# ORD_POT.net
KiCad netlist of a schematic drawn in Altium Designer
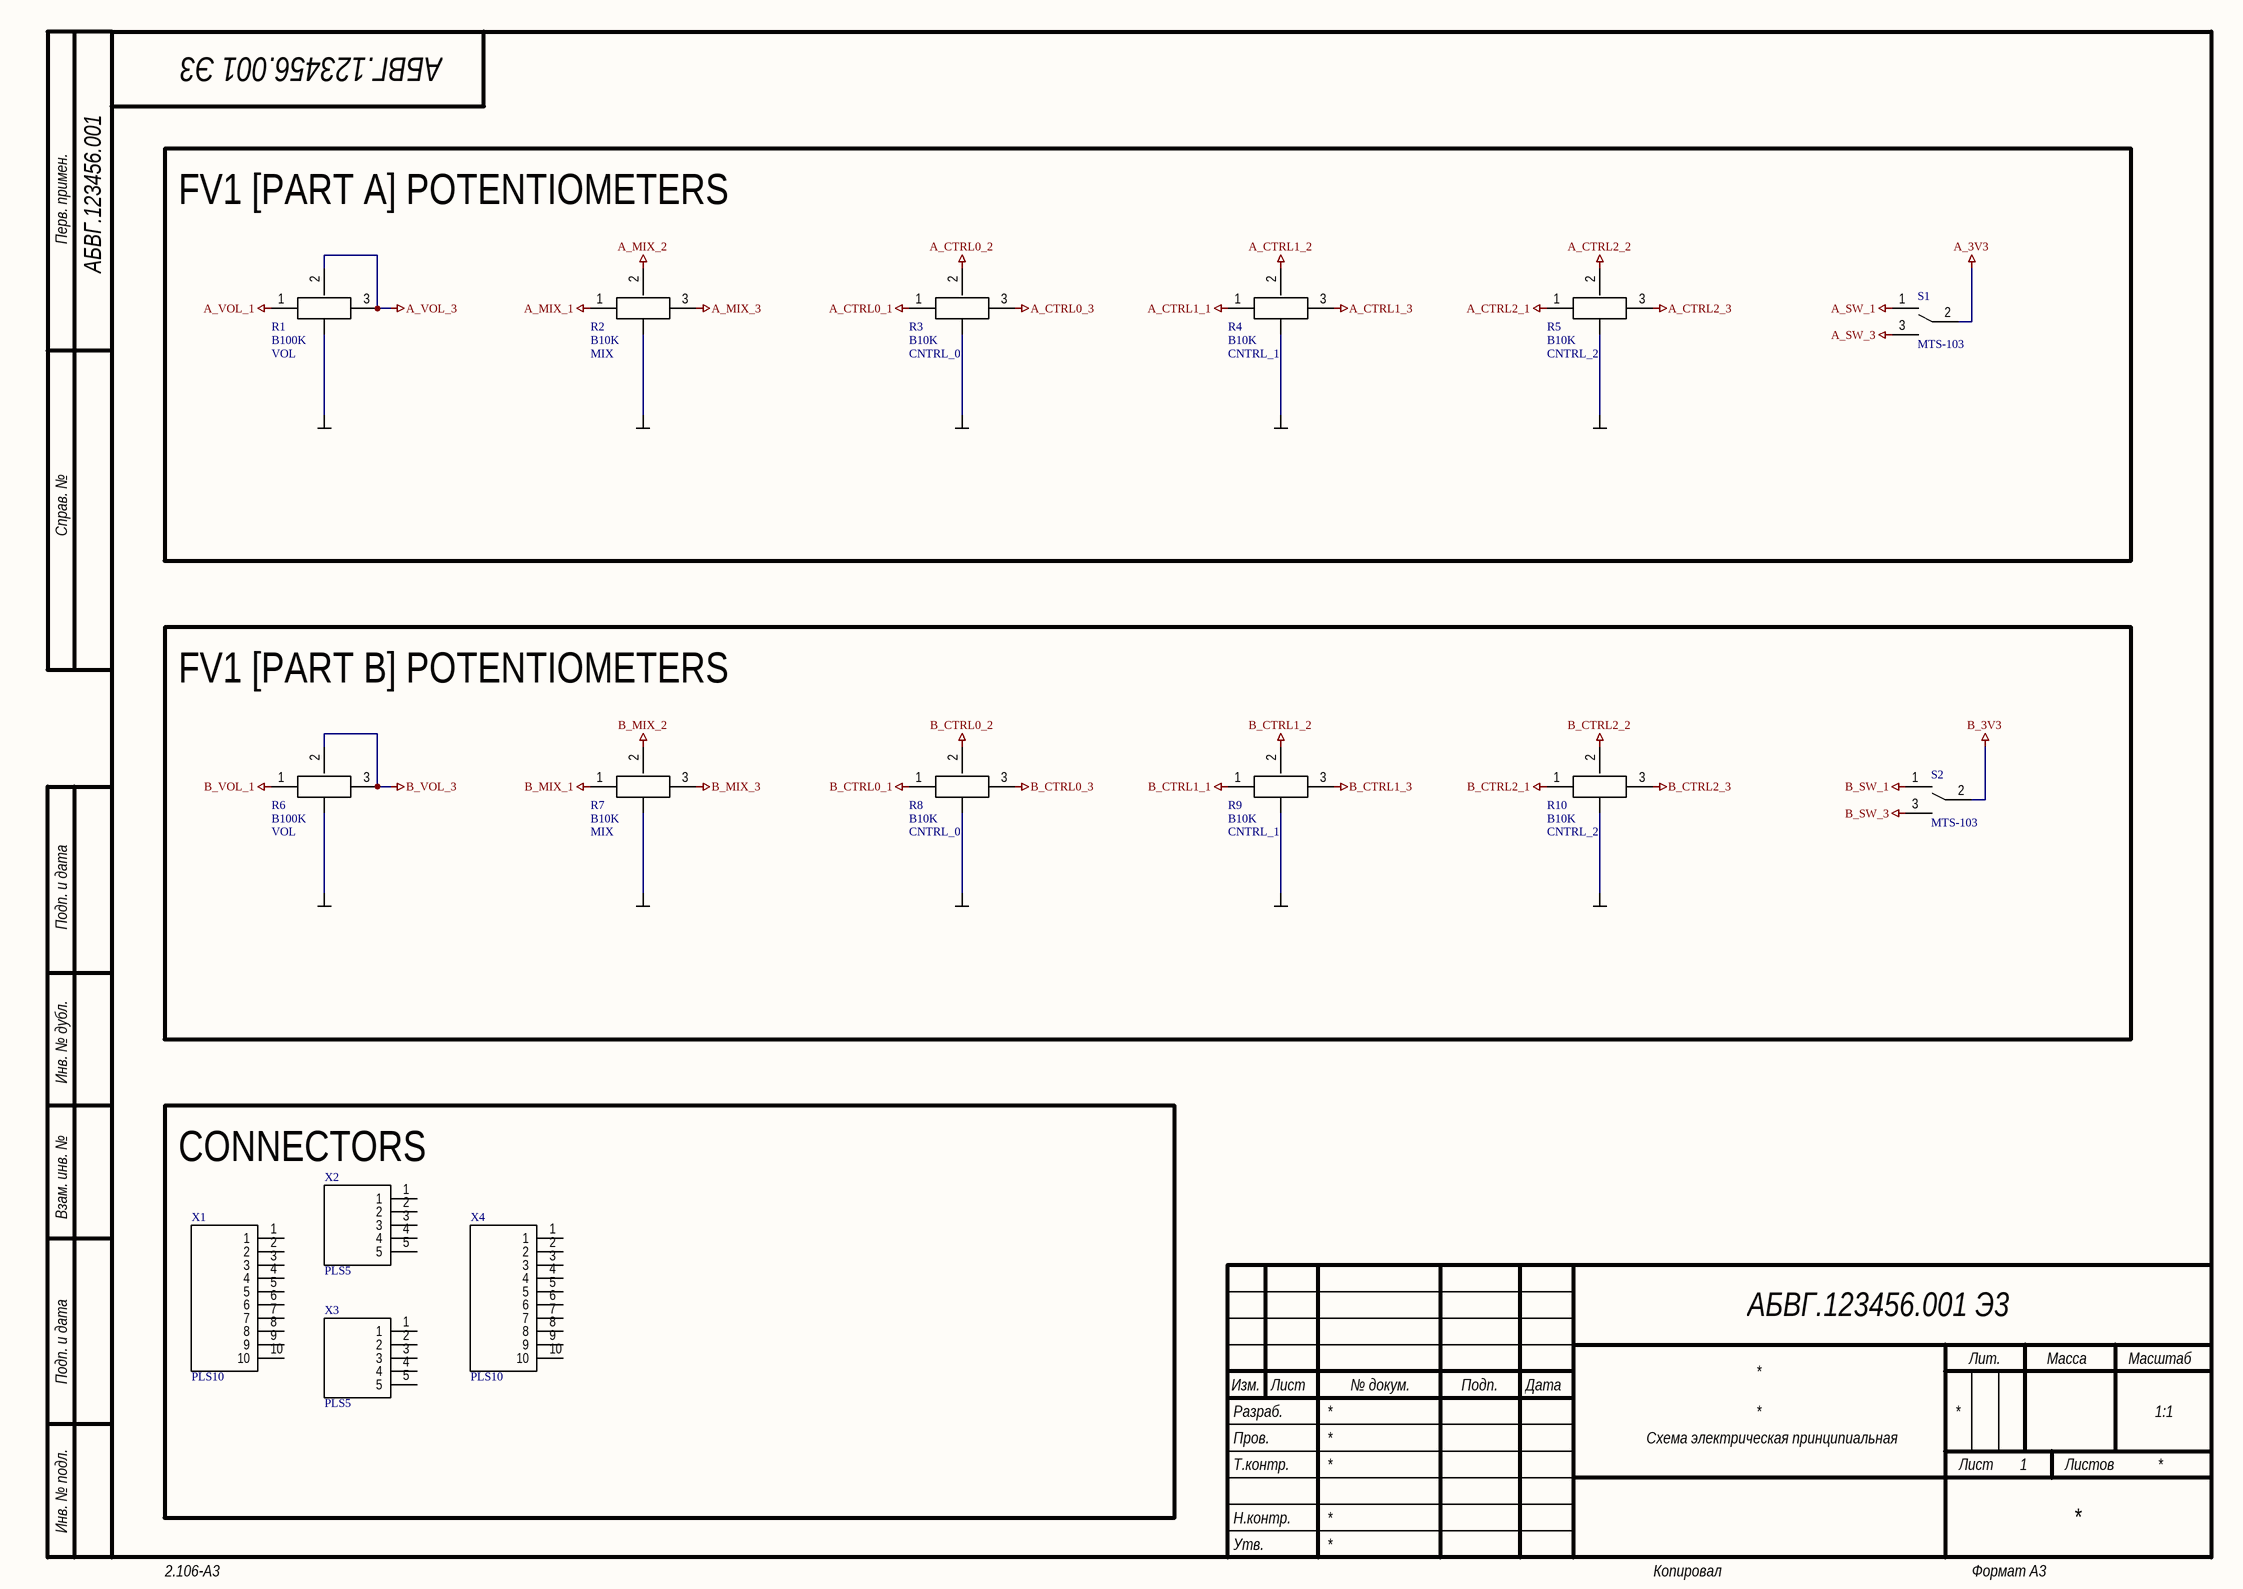
[diagram p0: ORD_POT.SchDoc]

(export (version "E")
  (design (tool "Eeschema 10.0.6"))
  (components
    (comp (ref "R1") (value "B100K") (footprint "RK097") (libsource (lib "Gost_passive_lib") (part "RK097")))
    (comp (ref "R2") (value "B10K") (footprint "RK097") (libsource (lib "Gost_passive_lib") (part "RK097")))
    (comp (ref "R3") (value "B10K") (footprint "RK097") (libsource (lib "Gost_passive_lib") (part "RK097")))
    (comp (ref "R4") (value "B10K") (footprint "RK097") (libsource (lib "Gost_passive_lib") (part "RK097")))
    (comp (ref "R5") (value "B10K") (footprint "RK097") (libsource (lib "Gost_passive_lib") (part "RK097")))
    (comp (ref "R6") (value "B100K") (footprint "RK097") (libsource (lib "Gost_passive_lib") (part "RK097")))
    (comp (ref "R7") (value "B10K") (footprint "RK097") (libsource (lib "Gost_passive_lib") (part "RK097")))
    (comp (ref "R8") (value "B10K") (footprint "RK097") (libsource (lib "Gost_passive_lib") (part "RK097")))
    (comp (ref "R9") (value "B10K") (footprint "RK097") (libsource (lib "Gost_passive_lib") (part "RK097")))
    (comp (ref "R10") (value "B10K") (footprint "RK097") (libsource (lib "Gost_passive_lib") (part "RK097")))
    (comp (ref "S1")
      (value "MTS-103")
      (footprint "MTS-103")
      (description "Switch, ON-OFF-ON")
      (libsource (lib "Gost_connectors_lib") (part "MTS-103"))
    )
    (comp (ref "S2")
      (value "MTS-103")
      (footprint "MTS-103")
      (description "Switch, ON-OFF-ON")
      (libsource (lib "Gost_connectors_lib") (part "MTS-103"))
    )
    (comp (ref "X1")
      (value "PLS10")
      (footprint "PLS-10")
      (description "2.54 mm")
      (libsource (lib "Gost_connectors_lib") (part "PLS10"))
    )
    (comp (ref "X2")
      (value "PLS5")
      (footprint "pls-5")
      (description "2.54 mm")
      (libsource (lib "Gost_connectors_lib") (part "PLS5"))
    )
    (comp (ref "X3")
      (value "PLS5")
      (footprint "pls-5")
      (description "2.54 mm")
      (libsource (lib "Gost_connectors_lib") (part "PLS5"))
    )
    (comp (ref "X4")
      (value "PLS10")
      (footprint "PLS-10")
      (description "2.54 mm")
      (libsource (lib "Gost_connectors_lib") (part "PLS10"))
    )
  )
  (nets
    (net (code "1") (name "A_3V3") (class "Default")
      (node (ref "S1") (pin "2") (pinfunction "2_2") (pintype "passive"))
    )
    (net (code "2") (name "A_CTRL0_1") (class "Default")
      (node (ref "R3") (pin "1") (pinfunction "1_1") (pintype "passive"))
    )
    (net (code "3") (name "A_CTRL0_2") (class "Default")
      (node (ref "R3") (pin "2") (pinfunction "2_2") (pintype "passive"))
    )
    (net (code "4") (name "A_CTRL0_3") (class "Default")
      (node (ref "R3") (pin "3") (pinfunction "3_3") (pintype "passive"))
    )
    (net (code "5") (name "A_CTRL1_1") (class "Default")
      (node (ref "R4") (pin "1") (pinfunction "1_1") (pintype "passive"))
    )
    (net (code "6") (name "A_CTRL1_2") (class "Default")
      (node (ref "R4") (pin "2") (pinfunction "2_2") (pintype "passive"))
    )
    (net (code "7") (name "A_CTRL1_3") (class "Default")
      (node (ref "R4") (pin "3") (pinfunction "3_3") (pintype "passive"))
    )
    (net (code "8") (name "A_CTRL2_1") (class "Default")
      (node (ref "R5") (pin "1") (pinfunction "1_1") (pintype "passive"))
    )
    (net (code "9") (name "A_CTRL2_2") (class "Default")
      (node (ref "R5") (pin "2") (pinfunction "2_2") (pintype "passive"))
    )
    (net (code "10") (name "A_CTRL2_3") (class "Default")
      (node (ref "R5") (pin "3") (pinfunction "3_3") (pintype "passive"))
    )
    (net (code "11") (name "A_MIX_1") (class "Default")
      (node (ref "R2") (pin "1") (pinfunction "1_1") (pintype "passive"))
    )
    (net (code "12") (name "A_MIX_2") (class "Default")
      (node (ref "R2") (pin "2") (pinfunction "2_2") (pintype "passive"))
    )
    (net (code "13") (name "A_MIX_3") (class "Default")
      (node (ref "R2") (pin "3") (pinfunction "3_3") (pintype "passive"))
    )
    (net (code "14") (name "A_SW_1") (class "Default")
      (node (ref "S1") (pin "1") (pinfunction "1_1") (pintype "passive"))
    )
    (net (code "15") (name "A_SW_3") (class "Default")
      (node (ref "S1") (pin "3") (pinfunction "3_3") (pintype "passive"))
    )
    (net (code "16") (name "A_VOL_1") (class "Default")
      (node (ref "R1") (pin "1") (pinfunction "1_1") (pintype "passive"))
    )
    (net (code "17") (name "A_VOL_3") (class "Default")
      (node (ref "R1") (pin "2") (pinfunction "2_2") (pintype "passive"))
      (node (ref "R1") (pin "3") (pinfunction "3_3") (pintype "passive"))
    )
    (net (code "18") (name "B_3V3") (class "Default")
      (node (ref "S2") (pin "2") (pinfunction "2_2") (pintype "passive"))
    )
    (net (code "19") (name "B_CTRL0_1") (class "Default")
      (node (ref "R8") (pin "1") (pinfunction "1_1") (pintype "passive"))
    )
    (net (code "20") (name "B_CTRL0_2") (class "Default")
      (node (ref "R8") (pin "2") (pinfunction "2_2") (pintype "passive"))
    )
    (net (code "21") (name "B_CTRL0_3") (class "Default")
      (node (ref "R8") (pin "3") (pinfunction "3_3") (pintype "passive"))
    )
    (net (code "22") (name "B_CTRL1_1") (class "Default")
      (node (ref "R9") (pin "1") (pinfunction "1_1") (pintype "passive"))
    )
    (net (code "23") (name "B_CTRL1_2") (class "Default")
      (node (ref "R9") (pin "2") (pinfunction "2_2") (pintype "passive"))
    )
    (net (code "24") (name "B_CTRL1_3") (class "Default")
      (node (ref "R9") (pin "3") (pinfunction "3_3") (pintype "passive"))
    )
    (net (code "25") (name "B_CTRL2_1") (class "Default")
      (node (ref "R10") (pin "1") (pinfunction "1_1") (pintype "passive"))
    )
    (net (code "26") (name "B_CTRL2_2") (class "Default")
      (node (ref "R10") (pin "2") (pinfunction "2_2") (pintype "passive"))
    )
    (net (code "27") (name "B_CTRL2_3") (class "Default")
      (node (ref "R10") (pin "3") (pinfunction "3_3") (pintype "passive"))
    )
    (net (code "28") (name "B_MIX_1") (class "Default")
      (node (ref "R7") (pin "1") (pinfunction "1_1") (pintype "passive"))
    )
    (net (code "29") (name "B_MIX_2") (class "Default")
      (node (ref "R7") (pin "2") (pinfunction "2_2") (pintype "passive"))
    )
    (net (code "30") (name "B_MIX_3") (class "Default")
      (node (ref "R7") (pin "3") (pinfunction "3_3") (pintype "passive"))
    )
    (net (code "31") (name "B_SW_1") (class "Default")
      (node (ref "S2") (pin "1") (pinfunction "1_1") (pintype "passive"))
    )
    (net (code "32") (name "B_SW_3") (class "Default")
      (node (ref "S2") (pin "3") (pinfunction "3_3") (pintype "passive"))
    )
    (net (code "33") (name "B_VOL_1") (class "Default")
      (node (ref "R6") (pin "1") (pinfunction "1_1") (pintype "passive"))
    )
    (net (code "34") (name "B_VOL_3") (class "Default")
      (node (ref "R6") (pin "2") (pinfunction "2_2") (pintype "passive"))
      (node (ref "R6") (pin "3") (pinfunction "3_3") (pintype "passive"))
    )
    (net (code "36") (name "unconnected-(R1-Pad4)") (class "Default")
      (node (ref "R1") (pin "4") (pinfunction "4_4") (pintype "passive"))
    )
    (net (code "37") (name "unconnected-(R2-Pad4)") (class "Default")
      (node (ref "R2") (pin "4") (pinfunction "4_4") (pintype "passive"))
    )
    (net (code "38") (name "unconnected-(R3-Pad4)") (class "Default")
      (node (ref "R3") (pin "4") (pinfunction "4_4") (pintype "passive"))
    )
    (net (code "39") (name "unconnected-(R4-Pad4)") (class "Default")
      (node (ref "R4") (pin "4") (pinfunction "4_4") (pintype "passive"))
    )
    (net (code "40") (name "unconnected-(R5-Pad4)") (class "Default")
      (node (ref "R5") (pin "4") (pinfunction "4_4") (pintype "passive"))
    )
    (net (code "41") (name "unconnected-(R6-Pad4)") (class "Default")
      (node (ref "R6") (pin "4") (pinfunction "4_4") (pintype "passive"))
    )
    (net (code "42") (name "unconnected-(R7-Pad4)") (class "Default")
      (node (ref "R7") (pin "4") (pinfunction "4_4") (pintype "passive"))
    )
    (net (code "43") (name "unconnected-(R8-Pad4)") (class "Default")
      (node (ref "R8") (pin "4") (pinfunction "4_4") (pintype "passive"))
    )
    (net (code "44") (name "unconnected-(R9-Pad4)") (class "Default")
      (node (ref "R9") (pin "4") (pinfunction "4_4") (pintype "passive"))
    )
    (net (code "45") (name "unconnected-(R10-Pad4)") (class "Default")
      (node (ref "R10") (pin "4") (pinfunction "4_4") (pintype "passive"))
    )
    (net (code "46") (name "unconnected-(X1-Pad1)") (class "Default")
      (node (ref "X1") (pin "1") (pinfunction "1_1") (pintype "power_in"))
    )
    (net (code "47") (name "unconnected-(X1-Pad2)") (class "Default")
      (node (ref "X1") (pin "2") (pinfunction "2_2") (pintype "power_in"))
    )
    (net (code "48") (name "unconnected-(X1-Pad3)") (class "Default")
      (node (ref "X1") (pin "3") (pinfunction "3_3") (pintype "power_in"))
    )
    (net (code "49") (name "unconnected-(X1-Pad4)") (class "Default")
      (node (ref "X1") (pin "4") (pinfunction "4_4") (pintype "power_in"))
    )
    (net (code "50") (name "unconnected-(X1-Pad5)") (class "Default")
      (node (ref "X1") (pin "5") (pinfunction "5_5") (pintype "power_in"))
    )
    (net (code "51") (name "unconnected-(X1-Pad6)") (class "Default")
      (node (ref "X1") (pin "6") (pinfunction "6_6") (pintype "power_in"))
    )
    (net (code "52") (name "unconnected-(X1-Pad7)") (class "Default")
      (node (ref "X1") (pin "7") (pinfunction "7_7") (pintype "power_in"))
    )
    (net (code "53") (name "unconnected-(X1-Pad8)") (class "Default")
      (node (ref "X1") (pin "8") (pinfunction "8_8") (pintype "power_in"))
    )
    (net (code "54") (name "unconnected-(X1-Pad9)") (class "Default")
      (node (ref "X1") (pin "9") (pinfunction "9_9") (pintype "power_in"))
    )
    (net (code "55") (name "unconnected-(X1-Pad10)") (class "Default")
      (node (ref "X1") (pin "10") (pinfunction "10_10") (pintype "power_in"))
    )
    (net (code "56") (name "unconnected-(X2-Pad1)") (class "Default")
      (node (ref "X2") (pin "1") (pinfunction "1_1") (pintype "power_in"))
    )
    (net (code "57") (name "unconnected-(X2-Pad2)") (class "Default")
      (node (ref "X2") (pin "2") (pinfunction "2_2") (pintype "power_in"))
    )
    (net (code "58") (name "unconnected-(X2-Pad3)") (class "Default")
      (node (ref "X2") (pin "3") (pinfunction "3_3") (pintype "power_in"))
    )
    (net (code "59") (name "unconnected-(X2-Pad4)") (class "Default")
      (node (ref "X2") (pin "4") (pinfunction "4_4") (pintype "power_in"))
    )
    (net (code "60") (name "unconnected-(X2-Pad5)") (class "Default")
      (node (ref "X2") (pin "5") (pinfunction "5_5") (pintype "power_in"))
    )
    (net (code "61") (name "unconnected-(X3-Pad1)") (class "Default")
      (node (ref "X3") (pin "1") (pinfunction "1_1") (pintype "power_in"))
    )
    (net (code "62") (name "unconnected-(X3-Pad2)") (class "Default")
      (node (ref "X3") (pin "2") (pinfunction "2_2") (pintype "power_in"))
    )
    (net (code "63") (name "unconnected-(X3-Pad3)") (class "Default")
      (node (ref "X3") (pin "3") (pinfunction "3_3") (pintype "power_in"))
    )
    (net (code "64") (name "unconnected-(X3-Pad4)") (class "Default")
      (node (ref "X3") (pin "4") (pinfunction "4_4") (pintype "power_in"))
    )
    (net (code "65") (name "unconnected-(X3-Pad5)") (class "Default")
      (node (ref "X3") (pin "5") (pinfunction "5_5") (pintype "power_in"))
    )
    (net (code "66") (name "unconnected-(X4-Pad1)") (class "Default")
      (node (ref "X4") (pin "1") (pinfunction "1_1") (pintype "power_in"))
    )
    (net (code "67") (name "unconnected-(X4-Pad2)") (class "Default")
      (node (ref "X4") (pin "2") (pinfunction "2_2") (pintype "power_in"))
    )
    (net (code "68") (name "unconnected-(X4-Pad3)") (class "Default")
      (node (ref "X4") (pin "3") (pinfunction "3_3") (pintype "power_in"))
    )
    (net (code "69") (name "unconnected-(X4-Pad4)") (class "Default")
      (node (ref "X4") (pin "4") (pinfunction "4_4") (pintype "power_in"))
    )
    (net (code "70") (name "unconnected-(X4-Pad5)") (class "Default")
      (node (ref "X4") (pin "5") (pinfunction "5_5") (pintype "power_in"))
    )
    (net (code "71") (name "unconnected-(X4-Pad6)") (class "Default")
      (node (ref "X4") (pin "6") (pinfunction "6_6") (pintype "power_in"))
    )
    (net (code "72") (name "unconnected-(X4-Pad7)") (class "Default")
      (node (ref "X4") (pin "7") (pinfunction "7_7") (pintype "power_in"))
    )
    (net (code "73") (name "unconnected-(X4-Pad8)") (class "Default")
      (node (ref "X4") (pin "8") (pinfunction "8_8") (pintype "power_in"))
    )
    (net (code "74") (name "unconnected-(X4-Pad9)") (class "Default")
      (node (ref "X4") (pin "9") (pinfunction "9_9") (pintype "power_in"))
    )
    (net (code "75") (name "unconnected-(X4-Pad10)") (class "Default")
      (node (ref "X4") (pin "10") (pinfunction "10_10") (pintype "power_in"))
    )
  )
)
